# LM61495RPHR_Buck.net
KiCad netlist of a schematic drawn in Altium Designer
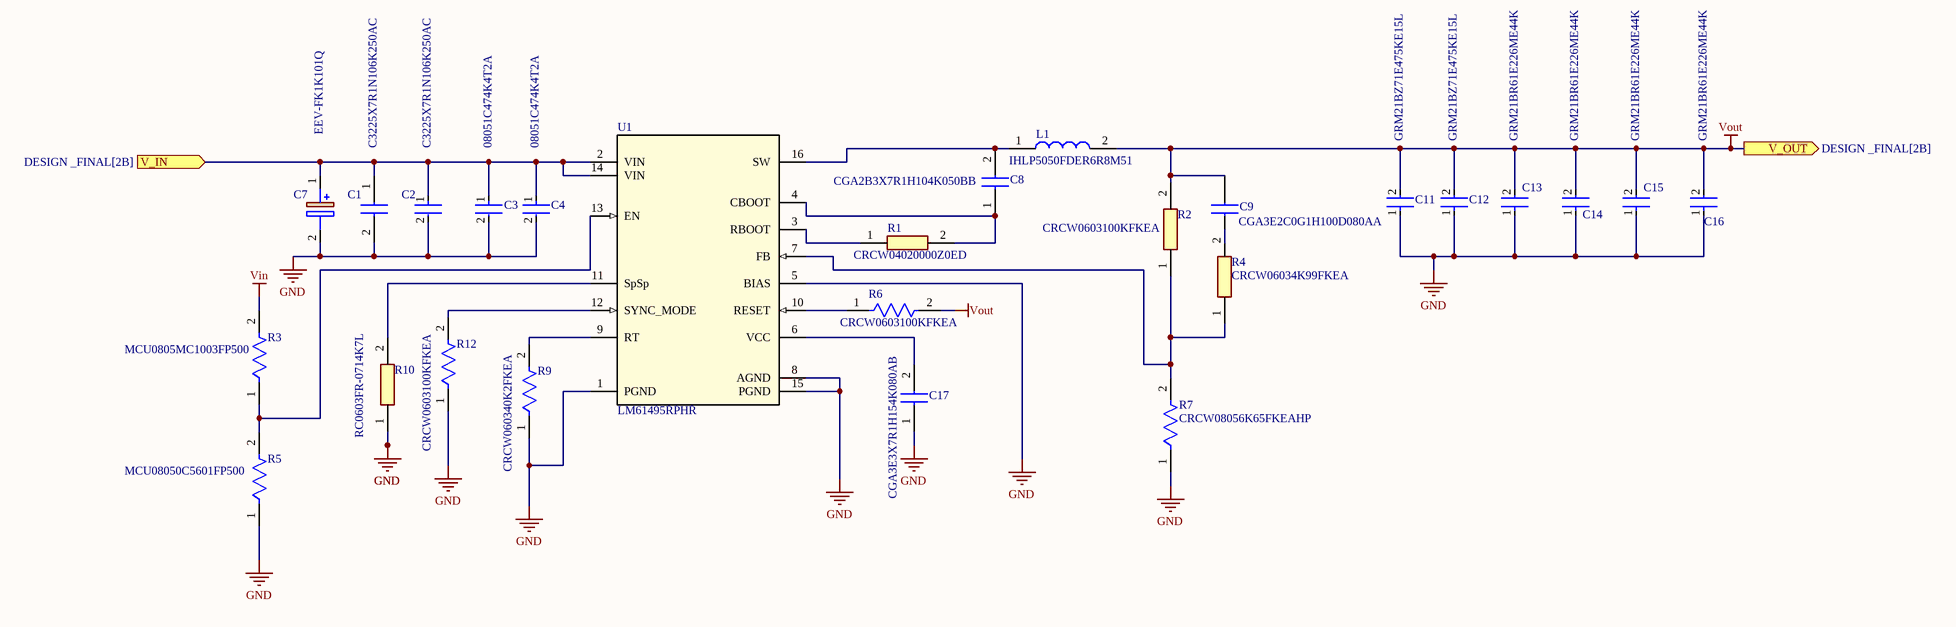
[diagram p0: LM61495RPHR_Buck.SchDoc]

(export (version "E")
  (design (tool "Eeschema 10.0.6"))
  (components
    (comp (ref "C1")
      (value "C3225X7R1N106K250AC")
      (footprint "SamacSys:CAPC3225X230N")
      (description "Capacitor")
      (fields (field (name "MOUSER PART NUMBER") "810-C3225X7R1N106K25"))
      (libsource (lib "*") (part "C3225X7R1N106K250AC"))
    )
    (comp (ref "C2")
      (value "C3225X7R1N106K250AC")
      (footprint "FP-C3225-250-0_4-IPC_A")
      (description "Multilayer Ceramic Capacitors 10uF ±10% 75V X7R SMD 1210")
      (libsource (lib "Altium Content Vault") (part "02cd4be3c70576c341d710602a673aa"))
    )
    (comp (ref "C3")
      (value "08051C474K4T2A")
      (footprint "FP-0805-L_2_01_0_2-W_1_25-MFG")
      (description "Automotive Ceramic Capacitor, 0805, 470nF, 10%, X7R, 15%, 100V")
      (fields (field (name "TOLERANCE") "10%"))
      (libsource (lib "Altium Content Vault") (part "b4654b650e69147ec39a6b967a45e02"))
    )
    (comp (ref "C4")
      (value "08051C474K4T2A")
      (footprint "FP-0805-L_2_01_0_2-W_1_25-MFG")
      (description "Automotive Ceramic Capacitor, 0805, 470nF, 10%, X7R, 15%, 100V")
      (fields (field (name "TOLERANCE") "10%"))
      (libsource (lib "Altium Content Vault") (part "b4654b650e69147ec39a6b967a45e02"))
    )
    (comp (ref "C7")
      (value "EEV-FK1K101Q")
      (footprint "SamacSys:EEEFK0J332AQ")
      (description "Capacitor Polarised")
      (fields (field (name "MOUSER PART NUMBER") "667-EEV-FK1K101Q"))
      (libsource (lib "*") (part "EEV-FK1K101Q"))
    )
    (comp (ref "C8")
      (value "CGA2B3X7R1H104K050BB")
      (footprint "SamacSys:CAPC1005X55N")
      (description "Capacitor")
      (fields (field (name "MOUSER PART NUMBER") "810-CGA2B3X7R1H104K"))
      (libsource (lib "*") (part "CGA2B3X7R1H104K050BB"))
    )
    (comp (ref "C9")
      (value "CGA3E2C0G1H100D080AA")
      (footprint "CAPC1608X90N")
      (description "TDK 0603 CGA 10pF Ceramic Multilayer Capacitor, 50 V dc, +125C, C0G Dielectric, +/-0.5pF")
      (fields (field (name "MOUSER PART NUMBER") "810-CGA3E2C0G1H100D"))
      (libsource (lib "CGA3E2C0G1H100D080AA") (part "CGA3E2C0G1H100D080AA_1"))
    )
    (comp (ref "C11")
      (value "GRM21BZ71E475KE15L")
      (footprint "FP-GRM21B-0_2-e0_2_0_7-MFG")
      (description "Chip Multilayer Ceramic Capacitors for General Purpose, 0805, 4.7uF, X7R, 15%, 10%, 25V")
      (libsource (lib "Altium Content Vault") (part "b4654b650e69147ec39a6b967a45e02"))
    )
    (comp (ref "C12")
      (value "GRM21BZ71E475KE15L")
      (footprint "FP-GRM21B-0_2-e0_2_0_7-MFG")
      (description "Chip Multilayer Ceramic Capacitors for General Purpose, 0805, 4.7uF, X7R, 15%, 10%, 25V")
      (libsource (lib "Altium Content Vault") (part "b4654b650e69147ec39a6b967a45e02"))
    )
    (comp (ref "C13")
      (value "GRM21BR61E226ME44K")
      (footprint "FP-GRM21B-0_2-e0_2_0_7-MFG")
      (description "Chip Multilayer Ceramic Capacitors for General Purpose, 0805, 22uF, X5R, 15%, 20%, 25V")
      (fields (field (name "TOLERANCE") "20%"))
      (libsource (lib "Altium Content Vault") (part "b4654b650e69147ec39a6b967a45e02"))
    )
    (comp (ref "C14")
      (value "GRM21BR61E226ME44K")
      (footprint "FP-GRM21B-0_2-e0_2_0_7-MFG")
      (description "Chip Multilayer Ceramic Capacitors for General Purpose, 0805, 22uF, X5R, 15%, 20%, 25V")
      (fields (field (name "TOLERANCE") "20%"))
      (libsource (lib "Altium Content Vault") (part "b4654b650e69147ec39a6b967a45e02"))
    )
    (comp (ref "C15")
      (value "GRM21BR61E226ME44K")
      (footprint "FP-GRM21B-0_2-e0_2_0_7-MFG")
      (description "Chip Multilayer Ceramic Capacitors for General Purpose, 0805, 22uF, X5R, 15%, 20%, 25V")
      (fields (field (name "TOLERANCE") "20%"))
      (libsource (lib "Altium Content Vault") (part "b4654b650e69147ec39a6b967a45e02"))
    )
    (comp (ref "C16")
      (value "GRM21BR61E226ME44K")
      (footprint "FP-GRM21B-0_2-e0_2_0_7-MFG")
      (description "Chip Multilayer Ceramic Capacitors for General Purpose, 0805, 22uF, X5R, 15%, 20%, 25V")
      (fields (field (name "TOLERANCE") "20%"))
      (libsource (lib "Altium Content Vault") (part "b4654b650e69147ec39a6b967a45e02"))
    )
    (comp (ref "C17")
      (value "CGA3E3X7R1H154K080AB")
      (footprint "SamacSys:GCM188")
      (description "CAP CER 0.15UF 50V X7R 0603")
      (fields
        (field (name "MANUFACTURER_PART_NUMBER") "GCM188R71C105MA64D")
        (field (name "MOUSER PART NUMBER") "81-GCM188R71C105MA4D")
      )
      (libsource (lib "*") (part "GCM188R71C105MA64D"))
    )
    (comp (ref "L1")
      (value "IHLP5050FDER6R8M51")
      (footprint "SamacSys:INDPM135129X640N")
      (description "Inductor")
      (fields (field (name "MOUSER PART NUMBER") "70-IHLP5050FDR6R8M51"))
      (libsource (lib "*") (part "IHLP5050FDER6R8M51"))
    )
    (comp (ref "R1")
      (value "CRCW04020000Z0ED")
      (footprint "SamacSys:RESC1005X40N")
      (description "Resistor")
      (fields
        (field (name "MANUFACTURER_PART_NUMBER") "CRCW04020000Z0EDHP")
        (field (name "MOUSER PART NUMBER") "71-CRCW04020000Z0EDH")
      )
      (libsource (lib "*") (part "CRCW04020000Z0EDHP"))
    )
    (comp (ref "R2")
      (value "CRCW0603100KFKEA")
      (footprint "SamacSys:RESC1608X50N")
      (description "Resistor")
      (fields (field (name "MOUSER PART NUMBER") "71-CRCW0603-100K-E3"))
      (libsource (lib "*") (part "CRCW0603100KFKEA"))
    )
    (comp (ref "R3")
      (value "MCU0805MC1003FP500")
      (footprint "FP-MCU0805-IPC_B")
      (description "RES 1.05K OHM 0.5% 1/5W 0805")
      (fields (field (name "TOLERANCE") "1%"))
      (libsource (lib "Altium Content Vault") (part "1029c3af85768c4190bb7ad29bc67b5"))
    )
    (comp (ref "R4")
      (value "CRCW06034K99FKEA")
      (footprint "SamacSys:RESC1608X50N")
      (description "Resistor")
      (fields (field (name "MOUSER PART NUMBER") "71-CRCW0603-4.99K-E3"))
      (libsource (lib "*") (part "CRCW06034K99FKEA"))
    )
    (comp (ref "R5")
      (value "MCU08050C5601FP500")
      (footprint "FP-MCU0805-IPC_B")
      (description "RES 1.05K OHM 0.5% 1/5W 0805")
      (fields (field (name "TOLERANCE") "1%"))
      (libsource (lib "Altium Content Vault") (part "1029c3af85768c4190bb7ad29bc67b5"))
    )
    (comp (ref "R6")
      (value "CRCW0603100KFKEA")
      (footprint "FP-CRCW0603C-e3-MFG")
      (description "RES SMD 100K OHM 1% 1/10W 0603")
      (fields (field (name "TOLERANCE") "1%"))
      (libsource (lib "Altium Content Vault") (part "1029c3af85768c4190bb7ad29bc67b5"))
    )
    (comp (ref "R7")
      (value "CRCW08056K65FKEAHP")
      (footprint "FP-CRCW0805-HPe3-IPC_C")
      (description "RES Thick Film, 6.65kΩ, 1%, 0.5W, 100ppm/°C, 0805")
      (fields (field (name "TOLERANCE") "1%"))
      (libsource (lib "Altium Content Vault") (part "1029c3af85768c4190bb7ad29bc67b5"))
    )
    (comp (ref "R9")
      (value "CRCW060340K2FKEA")
      (footprint "FP-CRCW0603-e3-IPC_B")
      (description "RES Thick Film, 40.2kΩ, 1%, 0.1W, 100ppm/°C, 0603")
      (fields (field (name "TOLERANCE") "1%"))
      (libsource (lib "Altium Content Vault") (part "1029c3af85768c4190bb7ad29bc67b5"))
    )
    (comp (ref "R10")
      (value "RC0603FR-0714K7L")
      (footprint "SamacSys:RESC1608X55N")
      (description "Resistor")
      (fields (field (name "MOUSER PART NUMBER") "603-RC0603FR-0714K7L"))
      (libsource (lib "*") (part "RC0603FR-0714K7L"))
    )
    (comp (ref "R12")
      (value "CRCW0603100KFKEA")
      (footprint "FP-CRCW0603C-e3-MFG")
      (description "RES SMD 100K OHM 1% 1/10W 0603")
      (fields (field (name "TOLERANCE") "1%"))
      (libsource (lib "Altium Content Vault") (part "1029c3af85768c4190bb7ad29bc67b5"))
    )
    (comp (ref "U1")
      (value "LM61495RPHR")
      (footprint "RPH0016A")
      (description "10-A buck converter optimized for power density and low EMI 16-VQFN-HR -40 to 150")
      (fields (field (name "COPYRIGHT") "Copyright (C) 2025 Ultra Librarian. All rights reserved."))
      (libsource (lib "Schlib1") (part "LM61495RPHR"))
    )
  )
  (nets
    (net (code "1") (name "/V_IN") (class "Default")
      (node (ref "C1") (pin "1") (pinfunction "1_1") (pintype "passive"))
      (node (ref "C2") (pin "1") (pinfunction "1_1") (pintype "passive"))
      (node (ref "C3") (pin "1") (pinfunction "1_1") (pintype "passive"))
      (node (ref "C4") (pin "1") (pinfunction "1_1") (pintype "passive"))
      (node (ref "C7") (pin "1") (pinfunction "+_1") (pintype "passive"))
      (node (ref "U1") (pin "14") (pinfunction "VIN_14") (pintype "power_in"))
      (node (ref "U1") (pin "2") (pinfunction "VIN_2") (pintype "power_in"))
    )
    (net (code "2") (name "GND") (class "Default")
      (node (ref "C1") (pin "2") (pinfunction "2_2") (pintype "passive"))
      (node (ref "C11") (pin "1") (pinfunction "1_1") (pintype "passive"))
      (node (ref "C12") (pin "1") (pinfunction "1_1") (pintype "passive"))
      (node (ref "C13") (pin "1") (pinfunction "1_1") (pintype "passive"))
      (node (ref "C14") (pin "1") (pinfunction "1_1") (pintype "passive"))
      (node (ref "C15") (pin "1") (pinfunction "1_1") (pintype "passive"))
      (node (ref "C16") (pin "1") (pinfunction "1_1") (pintype "passive"))
      (node (ref "C17") (pin "1") (pinfunction "1_1") (pintype "passive"))
      (node (ref "C2") (pin "2") (pinfunction "2_2") (pintype "passive"))
      (node (ref "C3") (pin "2") (pinfunction "2_2") (pintype "passive"))
      (node (ref "C4") (pin "2") (pinfunction "2_2") (pintype "passive"))
      (node (ref "C7") (pin "2") (pinfunction "-_2") (pintype "passive"))
      (node (ref "R10") (pin "1") (pinfunction "1_1") (pintype "passive"))
      (node (ref "R12") (pin "1") (pinfunction "1_1") (pintype "passive"))
      (node (ref "R5") (pin "1") (pinfunction "1_1") (pintype "passive"))
      (node (ref "R7") (pin "1") (pinfunction "1_1") (pintype "passive"))
      (node (ref "R9") (pin "1") (pinfunction "1_1") (pintype "passive"))
      (node (ref "U1") (pin "1") (pinfunction "PGND_1") (pintype "power_in"))
      (node (ref "U1") (pin "15") (pinfunction "PGND_15") (pintype "power_in"))
      (node (ref "U1") (pin "5") (pinfunction "BIAS_5") (pintype "passive"))
      (node (ref "U1") (pin "8") (pinfunction "AGND_8") (pintype "power_in"))
    )
    (net (code "3") (name "Net-(C9-Pad1)") (class "Default")
      (node (ref "C9") (pin "1") (pinfunction "1_1") (pintype "passive"))
      (node (ref "R4") (pin "2") (pinfunction "2_2") (pintype "passive"))
    )
    (net (code "4") (name "Net-(U1-CBOOT)") (class "Default")
      (node (ref "C8") (pin "1") (pinfunction "1_1") (pintype "passive"))
      (node (ref "R1") (pin "2") (pinfunction "2_2") (pintype "passive"))
      (node (ref "U1") (pin "4") (pinfunction "CBOOT_4") (pintype "passive"))
    )
    (net (code "5") (name "Net-(U1-EN)") (class "Default")
      (node (ref "R3") (pin "1") (pinfunction "1_1") (pintype "passive"))
      (node (ref "R5") (pin "2") (pinfunction "2_2") (pintype "passive"))
      (node (ref "U1") (pin "13") (pinfunction "EN_13") (pintype "input"))
    )
    (net (code "6") (name "Net-(U1-FB)") (class "Default")
      (node (ref "R2") (pin "1") (pinfunction "1_1") (pintype "passive"))
      (node (ref "R4") (pin "1") (pinfunction "1_1") (pintype "passive"))
      (node (ref "R7") (pin "2") (pinfunction "2_2") (pintype "passive"))
      (node (ref "U1") (pin "7") (pinfunction "FB_7") (pintype "input"))
    )
    (net (code "7") (name "Net-(U1-RBOOT)") (class "Default")
      (node (ref "R1") (pin "1") (pinfunction "1_1") (pintype "passive"))
      (node (ref "U1") (pin "3") (pinfunction "RBOOT_3") (pintype "passive"))
    )
    (net (code "8") (name "Net-(U1-RESET)") (class "Default")
      (node (ref "R6") (pin "1") (pinfunction "1_1") (pintype "passive"))
      (node (ref "U1") (pin "10") (pinfunction "RESET_10") (pintype "input"))
    )
    (net (code "9") (name "Net-(U1-RT)") (class "Default")
      (node (ref "R9") (pin "2") (pinfunction "2_2") (pintype "passive"))
      (node (ref "U1") (pin "9") (pinfunction "RT_9") (pintype "passive"))
    )
    (net (code "10") (name "Net-(U1-SW)") (class "Default")
      (node (ref "C8") (pin "2") (pinfunction "2_2") (pintype "passive"))
      (node (ref "L1") (pin "1") (pinfunction "1_1") (pintype "passive"))
      (node (ref "U1") (pin "16") (pinfunction "SW_16") (pintype "power_in"))
    )
    (net (code "11") (name "Net-(U1-SYNC_MODE)") (class "Default")
      (node (ref "R12") (pin "2") (pinfunction "2_2") (pintype "passive"))
      (node (ref "U1") (pin "12") (pinfunction "SYNC_MODE_12") (pintype "input"))
    )
    (net (code "12") (name "Net-(U1-SpSp)") (class "Default")
      (node (ref "R10") (pin "2") (pinfunction "2_2") (pintype "passive"))
      (node (ref "U1") (pin "11") (pinfunction "SpSp_11") (pintype "passive"))
    )
    (net (code "13") (name "Net-(U1-VCC)") (class "Default")
      (node (ref "C17") (pin "2") (pinfunction "2_2") (pintype "passive"))
      (node (ref "U1") (pin "6") (pinfunction "VCC_6") (pintype "power_in"))
    )
    (net (code "14") (name "Vin") (class "Default")
      (node (ref "R3") (pin "2") (pinfunction "2_2") (pintype "passive"))
    )
    (net (code "15") (name "Vout") (class "Default")
      (node (ref "C11") (pin "2") (pinfunction "2_2") (pintype "passive"))
      (node (ref "C12") (pin "2") (pinfunction "2_2") (pintype "passive"))
      (node (ref "C13") (pin "2") (pinfunction "2_2") (pintype "passive"))
      (node (ref "C14") (pin "2") (pinfunction "2_2") (pintype "passive"))
      (node (ref "C15") (pin "2") (pinfunction "2_2") (pintype "passive"))
      (node (ref "C16") (pin "2") (pinfunction "2_2") (pintype "passive"))
      (node (ref "C9") (pin "2") (pinfunction "2_2") (pintype "passive"))
      (node (ref "L1") (pin "2") (pinfunction "2_2") (pintype "passive"))
      (node (ref "R2") (pin "2") (pinfunction "2_2") (pintype "passive"))
      (node (ref "R6") (pin "2") (pinfunction "2_2") (pintype "passive"))
    )
  )
)
